# connector.net
KiCad netlist of a schematic drawn in Altium Designer
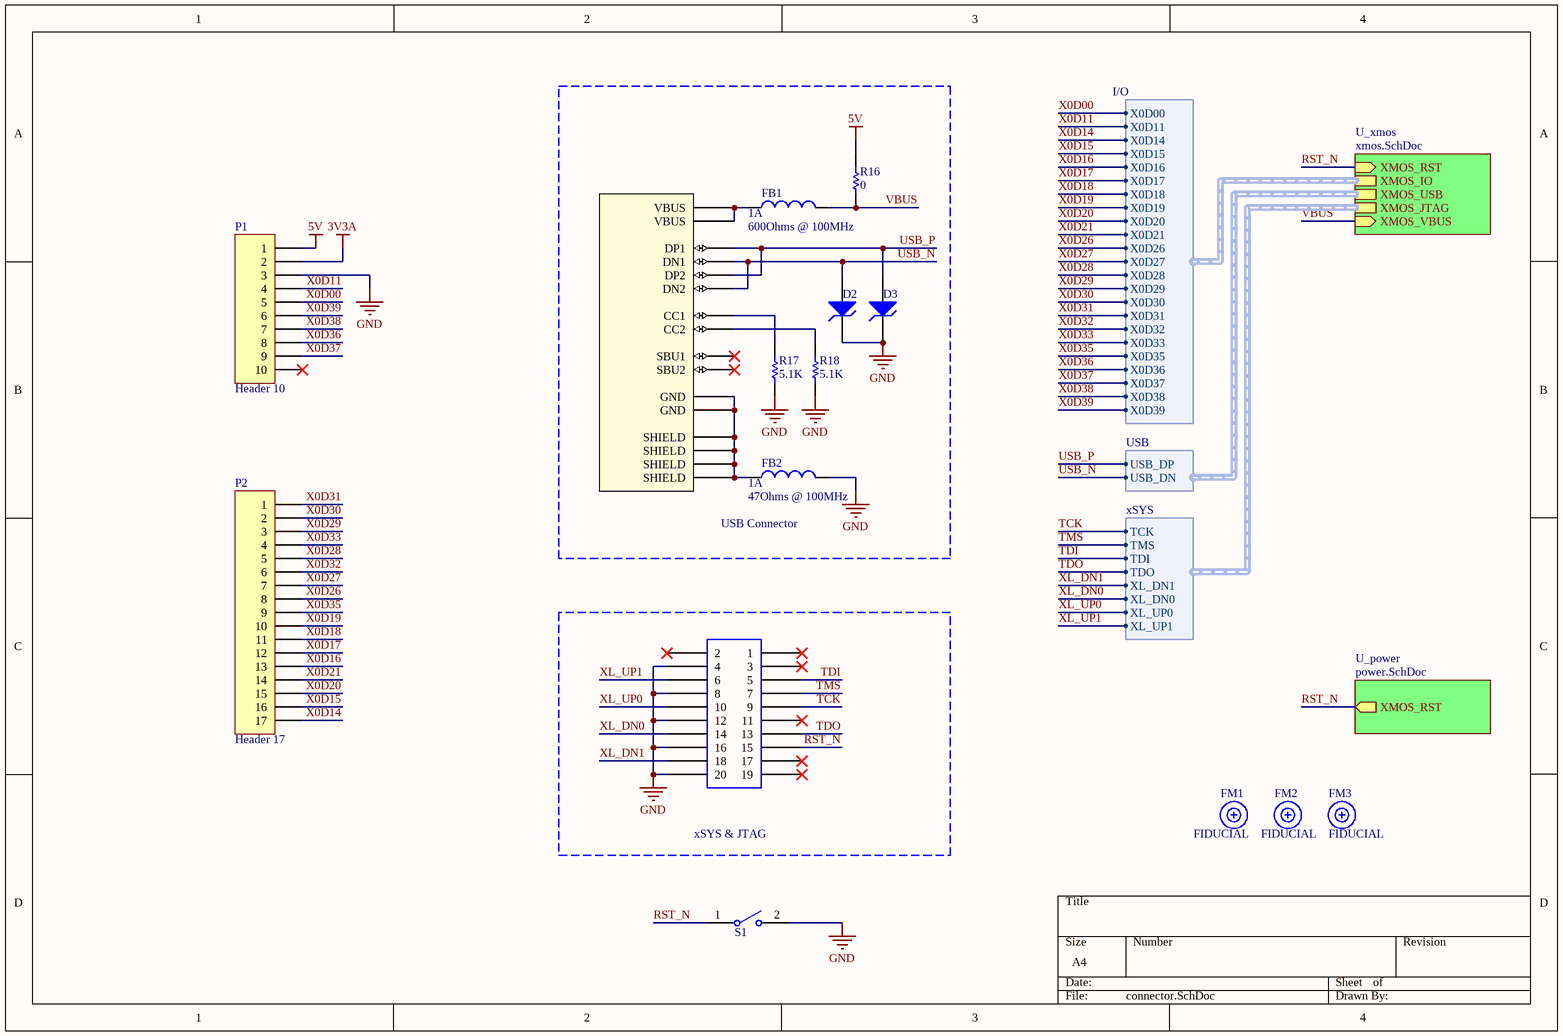
[diagram p0: connector.SchDoc]

(export (version "E")
  (design (tool "Eeschema 10.0.6"))
  (components
    (comp (ref "D2")
      (value "ESD9B")
      (footprint "SOD-923-2")
      (description "ESD Protection Diode")
      (libsource (lib "ON") (part "ESD9B"))
    )
    (comp (ref "D3")
      (value "ESD9B")
      (footprint "SOD-923-2")
      (description "ESD Protection Diode")
      (libsource (lib "ON") (part "ESD9B"))
    )
    (comp (ref "FB1")
      (value "Ferrite")
      (footprint "IND_1608")
      (description "Ferrite Beads")
      (fields (field (name "IMPEDANCE") "600Ohms @ 100MHz") (field (name "MAXIMUMDCCURRENT") "1A"))
      (libsource (lib "Inductors") (part "Ferrite"))
    )
    (comp (ref "FB2")
      (value "Ferrite")
      (footprint "IND_1608")
      (description "Ferrite Beads")
      (fields (field (name "IMPEDANCE") "47Ohms @ 100MHz") (field (name "MAXIMUMDCCURRENT") "1A"))
      (libsource (lib "Inductors") (part "Ferrite"))
    )
    (comp (ref "FM1")
      (value "FIDUCIAL")
      (footprint "FIDUCIAL_10_20")
      (description "Fiducial, dot")
      (libsource (lib "Fiducial") (part "FIDUCIAL"))
    )
    (comp (ref "FM2")
      (value "FIDUCIAL")
      (footprint "FIDUCIAL_10_20")
      (description "Fiducial, dot")
      (libsource (lib "Fiducial") (part "FIDUCIAL"))
    )
    (comp (ref "FM3")
      (value "FIDUCIAL")
      (footprint "FIDUCIAL_10_20")
      (description "Fiducial, dot")
      (libsource (lib "Fiducial") (part "FIDUCIAL"))
    )
    (comp (ref "J1")
      (value "USB C RECEPTACLE(1)")
      (footprint "USB C RECEPTACLE 2(1)")
      (description "Universal Serial Bus (USB) I/O Receptacle, Type C, 2.0")
      (libsource (lib "Connectors") (part "USB C RECEPTACLE(1)"))
    )
    (comp (ref "J2")
      (value "DC3-20P")
      (footprint "IDC-20 (1)")
      (description "20-Pin Shrouded Header (IDC) Right Angle")
      (libsource (lib "Connectors") (part "DC3-20P"))
    )
    (comp (ref "P1")
      (value "Header 10")
      (footprint "HDR1X10")
      (description "Header, 10-Pin")
      (fields (field (name "PUBLISHER") "Altium Limited"))
      (libsource (lib "Miscellaneous Connectors") (part "Header 10"))
    )
    (comp (ref "P2")
      (value "Header 17")
      (footprint "HDR1X17")
      (description "Header, 17-Pin")
      (fields (field (name "PUBLISHER") "Altium Limited"))
      (libsource (lib "Miscellaneous Connectors") (part "Header 17"))
    )
    (comp (ref "R16")
      (value "0")
      (footprint "RC0603N")
      (description "Chip Resistors")
      (fields (field (name "Comment") "RES"))
      (libsource (lib "Resistors") (part "RES"))
    )
    (comp (ref "R17")
      (value "5.1K")
      (footprint "RC0603N")
      (description "Chip Resistors")
      (fields (field (name "Comment") "RES"))
      (libsource (lib "Resistors") (part "RES"))
    )
    (comp (ref "R18")
      (value "5.1K")
      (footprint "RC0603N")
      (description "Chip Resistors")
      (fields (field (name "Comment") "RES"))
      (libsource (lib "Resistors") (part "RES"))
    )
    (comp (ref "S1")
      (value "Tact Switch SPST")
      (footprint "TS_SPST_W4.2XD3.2")
      (description "Switch")
      (libsource (lib "Switches") (part "Tact Switch SPST"))
    )
  )
  (nets
    (net (code "4") (name "/RST_N") (class "Default")
      (node (ref "J2") (pin "15") (pinfunction "15_15") (pintype "passive"))
      (node (ref "S1") (pin "1") (pinfunction "1_1") (pintype "passive"))
    )
    (net (code "5") (name "/TCK") (class "Default")
      (node (ref "J2") (pin "9") (pinfunction "9_9") (pintype "passive"))
    )
    (net (code "6") (name "/TDI") (class "Default")
      (node (ref "J2") (pin "5") (pinfunction "5_5") (pintype "passive"))
    )
    (net (code "7") (name "/TDO") (class "Default")
      (node (ref "J2") (pin "13") (pinfunction "13_13") (pintype "passive"))
    )
    (net (code "8") (name "/TMS") (class "Default")
      (node (ref "J2") (pin "7") (pinfunction "7_7") (pintype "passive"))
    )
    (net (code "9") (name "/USB_N") (class "Default")
      (node (ref "D2") (pin "1") (pinfunction "1_1") (pintype "passive"))
      (node (ref "J1") (pin "A7") (pinfunction "DN1_A7") (pintype "bidirectional"))
      (node (ref "J1") (pin "B7") (pinfunction "DN2_B7") (pintype "bidirectional"))
    )
    (net (code "10") (name "/USB_P") (class "Default")
      (node (ref "D3") (pin "1") (pinfunction "1_1") (pintype "passive"))
      (node (ref "J1") (pin "A6") (pinfunction "DP1_A6") (pintype "bidirectional"))
      (node (ref "J1") (pin "B6") (pinfunction "DP2_B6") (pintype "bidirectional"))
    )
    (net (code "11") (name "/VBUS") (class "Default")
      (node (ref "FB1") (pin "2") (pinfunction "2_2") (pintype "passive"))
      (node (ref "R16") (pin "1") (pinfunction "1_1") (pintype "passive"))
    )
    (net (code "12") (name "/X0D00") (class "Default")
      (node (ref "P1") (pin "5") (pinfunction "5_5") (pintype "passive"))
    )
    (net (code "13") (name "/X0D11") (class "Default")
      (node (ref "P1") (pin "4") (pinfunction "4_4") (pintype "passive"))
    )
    (net (code "14") (name "/X0D14") (class "Default")
      (node (ref "P2") (pin "17") (pinfunction "17_17") (pintype "passive"))
    )
    (net (code "15") (name "/X0D15") (class "Default")
      (node (ref "P2") (pin "16") (pinfunction "16_16") (pintype "passive"))
    )
    (net (code "16") (name "/X0D16") (class "Default")
      (node (ref "P2") (pin "13") (pinfunction "13_13") (pintype "passive"))
    )
    (net (code "17") (name "/X0D17") (class "Default")
      (node (ref "P2") (pin "12") (pinfunction "12_12") (pintype "passive"))
    )
    (net (code "18") (name "/X0D18") (class "Default")
      (node (ref "P2") (pin "11") (pinfunction "11_11") (pintype "passive"))
    )
    (net (code "19") (name "/X0D19") (class "Default")
      (node (ref "P2") (pin "10") (pinfunction "10_10") (pintype "passive"))
    )
    (net (code "20") (name "/X0D20") (class "Default")
      (node (ref "P2") (pin "15") (pinfunction "15_15") (pintype "passive"))
    )
    (net (code "21") (name "/X0D21") (class "Default")
      (node (ref "P2") (pin "14") (pinfunction "14_14") (pintype "passive"))
    )
    (net (code "22") (name "/X0D26") (class "Default")
      (node (ref "P2") (pin "8") (pinfunction "8_8") (pintype "passive"))
    )
    (net (code "23") (name "/X0D27") (class "Default")
      (node (ref "P2") (pin "7") (pinfunction "7_7") (pintype "passive"))
    )
    (net (code "24") (name "/X0D28") (class "Default")
      (node (ref "P2") (pin "5") (pinfunction "5_5") (pintype "passive"))
    )
    (net (code "25") (name "/X0D29") (class "Default")
      (node (ref "P2") (pin "3") (pinfunction "3_3") (pintype "passive"))
    )
    (net (code "26") (name "/X0D30") (class "Default")
      (node (ref "P2") (pin "2") (pinfunction "2_2") (pintype "passive"))
    )
    (net (code "27") (name "/X0D31") (class "Default")
      (node (ref "P2") (pin "1") (pinfunction "1_1") (pintype "passive"))
    )
    (net (code "28") (name "/X0D32") (class "Default")
      (node (ref "P2") (pin "6") (pinfunction "6_6") (pintype "passive"))
    )
    (net (code "29") (name "/X0D33") (class "Default")
      (node (ref "P2") (pin "4") (pinfunction "4_4") (pintype "passive"))
    )
    (net (code "30") (name "/X0D35") (class "Default")
      (node (ref "P2") (pin "9") (pinfunction "9_9") (pintype "passive"))
    )
    (net (code "31") (name "/X0D36") (class "Default")
      (node (ref "P1") (pin "8") (pinfunction "8_8") (pintype "passive"))
    )
    (net (code "32") (name "/X0D37") (class "Default")
      (node (ref "P1") (pin "9") (pinfunction "9_9") (pintype "passive"))
    )
    (net (code "33") (name "/X0D38") (class "Default")
      (node (ref "P1") (pin "7") (pinfunction "7_7") (pintype "passive"))
    )
    (net (code "34") (name "/X0D39") (class "Default")
      (node (ref "P1") (pin "6") (pinfunction "6_6") (pintype "passive"))
    )
    (net (code "35") (name "/XL_DN0") (class "Default")
      (node (ref "J2") (pin "14") (pinfunction "14_14") (pintype "passive"))
    )
    (net (code "36") (name "/XL_DN1") (class "Default")
      (node (ref "J2") (pin "18") (pinfunction "18_18") (pintype "passive"))
    )
    (net (code "37") (name "/XL_UP0") (class "Default")
      (node (ref "J2") (pin "10") (pinfunction "10_10") (pintype "passive"))
    )
    (net (code "38") (name "/XL_UP1") (class "Default")
      (node (ref "J2") (pin "6") (pinfunction "6_6") (pintype "passive"))
    )
    (net (code "42") (name "3V3A") (class "Default")
      (node (ref "P1") (pin "2") (pinfunction "2_2") (pintype "passive"))
    )
    (net (code "43") (name "5V") (class "Default")
      (node (ref "P1") (pin "1") (pinfunction "1_1") (pintype "passive"))
      (node (ref "R16") (pin "2") (pinfunction "2_2") (pintype "passive"))
    )
    (net (code "44") (name "GND") (class "Default")
      (node (ref "D2") (pin "2") (pinfunction "2_2") (pintype "passive"))
      (node (ref "D3") (pin "2") (pinfunction "2_2") (pintype "passive"))
      (node (ref "FB2") (pin "2") (pinfunction "2_2") (pintype "passive"))
      (node (ref "J2") (pin "12") (pinfunction "12_12") (pintype "passive"))
      (node (ref "J2") (pin "16") (pinfunction "16_16") (pintype "passive"))
      (node (ref "J2") (pin "20") (pinfunction "20_20") (pintype "passive"))
      (node (ref "J2") (pin "4") (pinfunction "4_4") (pintype "passive"))
      (node (ref "J2") (pin "8") (pinfunction "8_8") (pintype "passive"))
      (node (ref "P1") (pin "3") (pinfunction "3_3") (pintype "passive"))
      (node (ref "R17") (pin "1") (pinfunction "1_1") (pintype "passive"))
      (node (ref "R18") (pin "1") (pinfunction "1_1") (pintype "passive"))
      (node (ref "S1") (pin "2") (pinfunction "2_2") (pintype "passive"))
    )
    (net (code "45") (name "Net-(FB1-Pad1)") (class "Default")
      (node (ref "FB1") (pin "1") (pinfunction "1_1") (pintype "passive"))
      (node (ref "J1") (pin "A4/B9") (pinfunction "VBUS_A4/B9") (pintype "power_in"))
      (node (ref "J1") (pin "B4/A9") (pinfunction "VBUS_B4/A9") (pintype "power_in"))
    )
    (net (code "46") (name "Net-(FB2-Pad1)") (class "Default")
      (node (ref "FB2") (pin "1") (pinfunction "1_1") (pintype "passive"))
      (node (ref "J1") (pin "A1/B12") (pinfunction "GND_A1/B12") (pintype "passive"))
      (node (ref "J1") (pin "B1/A12") (pinfunction "GND_B1/A12") (pintype "passive"))
      (node (ref "J1") (pin "SH1") (pinfunction "SHIELD_SH1") (pintype "passive"))
      (node (ref "J1") (pin "SH2") (pinfunction "SHIELD_SH2") (pintype "passive"))
      (node (ref "J1") (pin "SH3") (pinfunction "SHIELD_SH3") (pintype "passive"))
      (node (ref "J1") (pin "SH4") (pinfunction "SHIELD_SH4") (pintype "passive"))
    )
    (net (code "47") (name "Net-(J1-CC1)") (class "Default")
      (node (ref "J1") (pin "A5") (pinfunction "CC1_A5") (pintype "bidirectional"))
      (node (ref "R17") (pin "2") (pinfunction "2_2") (pintype "passive"))
    )
    (net (code "48") (name "Net-(J1-CC2)") (class "Default")
      (node (ref "J1") (pin "B5") (pinfunction "CC2_B5") (pintype "bidirectional"))
      (node (ref "R18") (pin "2") (pinfunction "2_2") (pintype "passive"))
    )
    (net (code "49") (name "unconnected-(J1-SBU1-PadA8)") (class "Default")
      (node (ref "J1") (pin "A8") (pinfunction "SBU1_A8") (pintype "bidirectional+no_connect"))
    )
    (net (code "50") (name "unconnected-(J1-SBU2-PadB8)") (class "Default")
      (node (ref "J1") (pin "B8") (pinfunction "SBU2_B8") (pintype "bidirectional+no_connect"))
    )
    (net (code "51") (name "unconnected-(J2-Pad1)") (class "Default")
      (node (ref "J2") (pin "1") (pinfunction "1_1") (pintype "passive+no_connect"))
    )
    (net (code "52") (name "unconnected-(J2-Pad2)") (class "Default")
      (node (ref "J2") (pin "2") (pinfunction "2_2") (pintype "passive+no_connect"))
    )
    (net (code "53") (name "unconnected-(J2-Pad3)") (class "Default")
      (node (ref "J2") (pin "3") (pinfunction "3_3") (pintype "passive+no_connect"))
    )
    (net (code "54") (name "unconnected-(J2-Pad11)") (class "Default")
      (node (ref "J2") (pin "11") (pinfunction "11_11") (pintype "passive+no_connect"))
    )
    (net (code "55") (name "unconnected-(J2-Pad17)") (class "Default")
      (node (ref "J2") (pin "17") (pinfunction "17_17") (pintype "passive+no_connect"))
    )
    (net (code "56") (name "unconnected-(J2-Pad19)") (class "Default")
      (node (ref "J2") (pin "19") (pinfunction "19_19") (pintype "passive+no_connect"))
    )
    (net (code "57") (name "unconnected-(P1-Pad10)") (class "Default")
      (node (ref "P1") (pin "10") (pinfunction "10_10") (pintype "passive+no_connect"))
    )
  )
)
